# Adafruit_7in_HDMI_Backpack.net
KiCad netlist of a schematic drawn in EAGLE
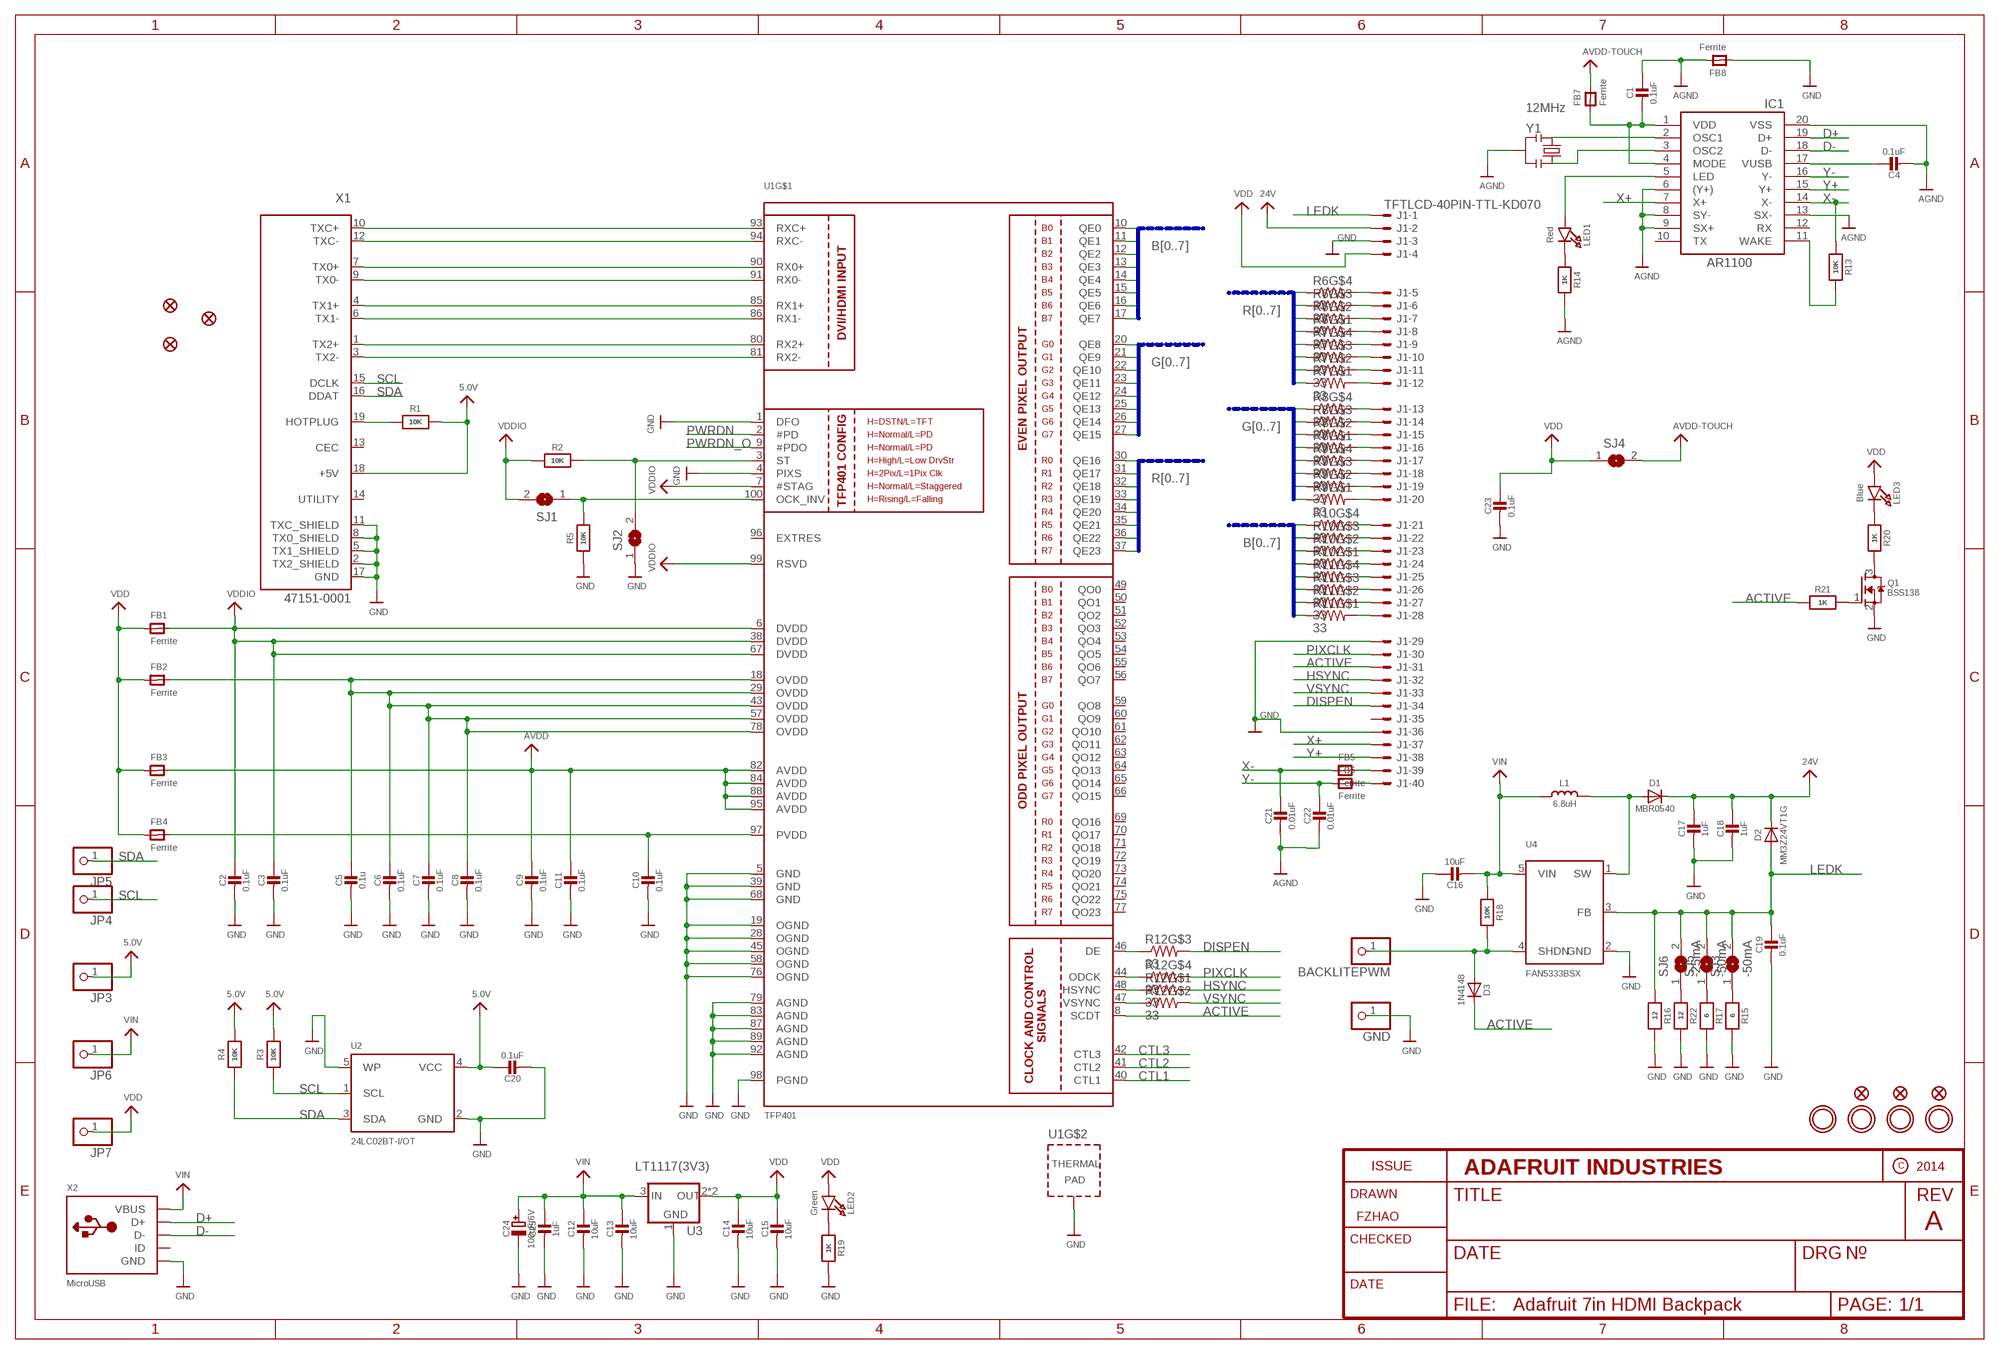
[diagram p0: schematic, sheet 1]

(export (version "E")
  (design (tool "Eeschema 10.0.6"))
  (components
    (comp (ref "BACKLITEPWM")
      (value "HEADER-1X1-SMD_MASKHELD_2X2MM")
      (footprint "eagle-import:1X01_SMD_MASKHELD_2X2MM")
      (libsource (lib "eagle-import") (part "HEADER-1X1-SMD_MASKHELD_2X2MM"))
    )
    (comp (ref "C1")
      (value "0.1uF")
      (footprint "eagle-import:0805-NO")
      (libsource (lib "eagle-import") (part "CAP_CERAMIC0805-NOOUTLINE"))
    )
    (comp (ref "C2")
      (value "0.1uF")
      (footprint "eagle-import:0805-NO")
      (libsource (lib "eagle-import") (part "CAP_CERAMIC0805-NOOUTLINE"))
    )
    (comp (ref "C3")
      (value "0.1uF")
      (footprint "eagle-import:0805-NO")
      (libsource (lib "eagle-import") (part "CAP_CERAMIC0805-NOOUTLINE"))
    )
    (comp (ref "C4")
      (value "0.1uF")
      (footprint "eagle-import:_0805MP")
      (libsource (lib "eagle-import") (part "CAP_CERAMIC_0805MP"))
    )
    (comp (ref "C5")
      (value "0.1u")
      (footprint "eagle-import:0805-NO")
      (libsource (lib "eagle-import") (part "CAP_CERAMIC0805-NOOUTLINE"))
    )
    (comp (ref "C6")
      (value "0.1uF")
      (footprint "eagle-import:_0805MP")
      (libsource (lib "eagle-import") (part "CAP_CERAMIC_0805MP"))
    )
    (comp (ref "C7")
      (value "0.1uF")
      (footprint "eagle-import:0805-NO")
      (libsource (lib "eagle-import") (part "CAP_CERAMIC0805-NOOUTLINE"))
    )
    (comp (ref "C8")
      (value "0.1uF")
      (footprint "eagle-import:0805-NO")
      (libsource (lib "eagle-import") (part "CAP_CERAMIC0805-NOOUTLINE"))
    )
    (comp (ref "C9")
      (value "0.1uF")
      (footprint "eagle-import:0805-NO")
      (libsource (lib "eagle-import") (part "CAP_CERAMIC0805-NOOUTLINE"))
    )
    (comp (ref "C10")
      (value "0.1uF")
      (footprint "eagle-import:0805-NO")
      (libsource (lib "eagle-import") (part "CAP_CERAMIC0805-NOOUTLINE"))
    )
    (comp (ref "C11")
      (value "0.1uF")
      (footprint "eagle-import:0805-NO")
      (libsource (lib "eagle-import") (part "CAP_CERAMIC0805-NOOUTLINE"))
    )
    (comp (ref "C12")
      (value "10uF")
      (footprint "eagle-import:0805-NO")
      (libsource (lib "eagle-import") (part "CAP_CERAMIC0805-NOOUTLINE"))
    )
    (comp (ref "C13")
      (value "10uF")
      (footprint "eagle-import:0805-NO")
      (libsource (lib "eagle-import") (part "CAP_CERAMIC0805-NOOUTLINE"))
    )
    (comp (ref "C14")
      (value "10uF")
      (footprint "eagle-import:0805-NO")
      (libsource (lib "eagle-import") (part "CAP_CERAMIC0805-NOOUTLINE"))
    )
    (comp (ref "C15")
      (value "10uF")
      (footprint "eagle-import:0805-NO")
      (libsource (lib "eagle-import") (part "CAP_CERAMIC0805-NOOUTLINE"))
    )
    (comp (ref "C16")
      (value "10uF")
      (footprint "eagle-import:0805-NO")
      (libsource (lib "eagle-import") (part "CAP_CERAMIC0805-NOOUTLINE"))
    )
    (comp (ref "C17")
      (value "1uF")
      (footprint "eagle-import:0805-NO")
      (libsource (lib "eagle-import") (part "CAP_CERAMIC0805-NOOUTLINE"))
    )
    (comp (ref "C18")
      (value "1uF")
      (footprint "eagle-import:0805-NO")
      (libsource (lib "eagle-import") (part "CAP_CERAMIC0805-NOOUTLINE"))
    )
    (comp (ref "C19")
      (value "0.1uF")
      (footprint "eagle-import:0805-NO")
      (libsource (lib "eagle-import") (part "CAP_CERAMIC0805-NOOUTLINE"))
    )
    (comp (ref "C20")
      (value "0.1uF")
      (footprint "eagle-import:0805-NO")
      (libsource (lib "eagle-import") (part "CAP_CERAMIC0805-NOOUTLINE"))
    )
    (comp (ref "C21")
      (value "0.01uF")
      (footprint "eagle-import:0805-NO")
      (libsource (lib "eagle-import") (part "CAP_CERAMIC0805-NOOUTLINE"))
    )
    (comp (ref "C22")
      (value "0.01uF")
      (footprint "eagle-import:0805-NO")
      (libsource (lib "eagle-import") (part "CAP_CERAMIC0805-NOOUTLINE"))
    )
    (comp (ref "C23")
      (value "0.1uF")
      (footprint "eagle-import:0805-NO")
      (libsource (lib "eagle-import") (part "CAP_CERAMIC0805-NOOUTLINE"))
    )
    (comp (ref "C24")
      (value "100uF/6V")
      (footprint "eagle-import:PANASONIC_C")
      (libsource (lib "eagle-import") (part "CAP_ELECTROLYTICPANASONIC_C"))
    )
    (comp (ref "C25")
      (value "1uF")
      (footprint "eagle-import:0805-NO")
      (libsource (lib "eagle-import") (part "CAP_CERAMIC0805-NOOUTLINE"))
    )
    (comp (ref "D1")
      (value "MBR0540")
      (footprint "eagle-import:SOD-123")
      (libsource (lib "eagle-import") (part "DIODESOD-123"))
    )
    (comp (ref "D2")
      (value "MM3Z24VT1G")
      (footprint "eagle-import:SMADIODE")
      (libsource (lib "eagle-import") (part "DIODESMA"))
    )
    (comp (ref "D3")
      (value "1N4148")
      (footprint "eagle-import:SOD-323")
      (libsource (lib "eagle-import") (part "DIODESOD-323"))
    )
    (comp (ref "FB1")
      (value "Ferrite")
      (footprint "eagle-import:_0805MP")
      (libsource (lib "eagle-import") (part "FERRITE_0805MP"))
    )
    (comp (ref "FB2")
      (value "Ferrite")
      (footprint "eagle-import:_0805MP")
      (libsource (lib "eagle-import") (part "FERRITE_0805MP"))
    )
    (comp (ref "FB3")
      (value "Ferrite")
      (footprint "eagle-import:_0805MP")
      (libsource (lib "eagle-import") (part "FERRITE_0805MP"))
    )
    (comp (ref "FB4")
      (value "Ferrite")
      (footprint "eagle-import:_0805MP")
      (libsource (lib "eagle-import") (part "FERRITE_0805MP"))
    )
    (comp (ref "FB5")
      (value "Ferrite")
      (footprint "eagle-import:_0805MP")
      (libsource (lib "eagle-import") (part "FERRITE_0805MP"))
    )
    (comp (ref "FB6")
      (value "Ferrite")
      (footprint "eagle-import:_0805MP")
      (libsource (lib "eagle-import") (part "FERRITE_0805MP"))
    )
    (comp (ref "FB7")
      (value "Ferrite")
      (footprint "eagle-import:_0805MP")
      (libsource (lib "eagle-import") (part "FERRITE_0805MP"))
    )
    (comp (ref "FB8")
      (value "Ferrite")
      (footprint "eagle-import:_0805MP")
      (libsource (lib "eagle-import") (part "FERRITE_0805MP"))
    )
    (comp (ref "FID1")
      (value "FIDUCIAL\"\"")
      (footprint "eagle-import:FIDUCIAL_1MM")
      (libsource (lib "eagle-import") (part "FIDUCIAL{dblquote}{dblquote}"))
    )
    (comp (ref "FID2")
      (value "FIDUCIAL\"\"")
      (footprint "eagle-import:FIDUCIAL_1MM")
      (libsource (lib "eagle-import") (part "FIDUCIAL{dblquote}{dblquote}"))
    )
    (comp (ref "FID3")
      (value "FIDUCIAL\"\"")
      (footprint "eagle-import:FIDUCIAL_1MM")
      (libsource (lib "eagle-import") (part "FIDUCIAL{dblquote}{dblquote}"))
    )
    (comp (ref "FID4")
      (value "FIDUCIAL\"\"")
      (footprint "eagle-import:FIDUCIAL_1MM")
      (libsource (lib "eagle-import") (part "FIDUCIAL{dblquote}{dblquote}"))
    )
    (comp (ref "FID5")
      (value "FIDUCIAL\"\"")
      (footprint "eagle-import:FIDUCIAL_1MM")
      (libsource (lib "eagle-import") (part "FIDUCIAL{dblquote}{dblquote}"))
    )
    (comp (ref "FID6")
      (value "FIDUCIAL\"\"")
      (footprint "eagle-import:FIDUCIAL_1MM")
      (libsource (lib "eagle-import") (part "FIDUCIAL{dblquote}{dblquote}"))
    )
    (comp (ref "GND")
      (value "HEADER-1X1-SMD_MASKHELD_2X2MM")
      (footprint "eagle-import:1X01_SMD_MASKHELD_2X2MM")
      (libsource (lib "eagle-import") (part "HEADER-1X1-SMD_MASKHELD_2X2MM"))
    )
    (comp (ref "IC1")
      (value "AR1100")
      (footprint "eagle-import:TSSOP20-5.3MMBODY")
      (libsource (lib "eagle-import") (part "AR1100_SSOP"))
    )
    (comp (ref "J1")
      (value "TFTLCD-40PIN-TTL-KD070")
      (footprint "eagle-import:TFTLCD-KD070GD21-40NT")
      (libsource (lib "eagle-import") (part "TFTLCD-40PIN-TTL-KD070"))
    )
    (comp (ref "JP3")
      (value "HEADER-1X1-SMD_MASKHELD_2X2MM")
      (footprint "eagle-import:1X01_SMD_MASKHELD_2X2MM")
      (libsource (lib "eagle-import") (part "HEADER-1X1-SMD_MASKHELD_2X2MM"))
    )
    (comp (ref "JP4")
      (value "HEADER-1X1-SMD_MASKHELD_2X2MM")
      (footprint "eagle-import:1X01_SMD_MASKHELD_2X2MM")
      (libsource (lib "eagle-import") (part "HEADER-1X1-SMD_MASKHELD_2X2MM"))
    )
    (comp (ref "JP5")
      (value "HEADER-1X1-SMD_MASKHELD_2X2MM")
      (footprint "eagle-import:1X01_SMD_MASKHELD_2X2MM")
      (libsource (lib "eagle-import") (part "HEADER-1X1-SMD_MASKHELD_2X2MM"))
    )
    (comp (ref "JP6")
      (value "HEADER-1X1-SMD_MASKHELD_2X2MM")
      (footprint "eagle-import:1X01_SMD_MASKHELD_2X2MM")
      (libsource (lib "eagle-import") (part "HEADER-1X1-SMD_MASKHELD_2X2MM"))
    )
    (comp (ref "JP7")
      (value "HEADER-1X1-SMD_MASKHELD_2X2MM")
      (footprint "eagle-import:1X01_SMD_MASKHELD_2X2MM")
      (libsource (lib "eagle-import") (part "HEADER-1X1-SMD_MASKHELD_2X2MM"))
    )
    (comp (ref "L1")
      (value "6.8uH")
      (footprint "eagle-import:INDUCTOR_5X5MM_NR5040_NOTHERMALS")
      (libsource (lib "eagle-import") (part "INDUCTORNR5040"))
    )
    (comp (ref "LED1")
      (value "Red")
      (footprint "eagle-import:CHIPLED_0805_NOOUTLINE")
      (libsource (lib "eagle-import") (part "LED0805_NOOUTLINE"))
    )
    (comp (ref "LED2")
      (value "Green")
      (footprint "eagle-import:CHIPLED_0805_NOOUTLINE")
      (libsource (lib "eagle-import") (part "LED0805_NOOUTLINE"))
    )
    (comp (ref "LED3")
      (value "Blue")
      (footprint "eagle-import:CHIPLED_0805_NOOUTLINE")
      (libsource (lib "eagle-import") (part "LED0805_NOOUTLINE"))
    )
    (comp (ref "Q1")
      (value "BSS138")
      (footprint "eagle-import:SOT23-WIDE")
      (libsource (lib "eagle-import") (part "MOSFET-NWIDE"))
    )
    (comp (ref "R1")
      (value "10K")
      (footprint "eagle-import:0805-NO")
      (libsource (lib "eagle-import") (part "RESISTOR0805_NOOUTLINE"))
    )
    (comp (ref "R2")
      (value "10K")
      (footprint "eagle-import:_0805MP")
      (libsource (lib "eagle-import") (part "RESISTOR_0805MP"))
    )
    (comp (ref "R3")
      (value "10K")
      (footprint "eagle-import:0805-NO")
      (libsource (lib "eagle-import") (part "RESISTOR0805_NOOUTLINE"))
    )
    (comp (ref "R4")
      (value "10K")
      (footprint "eagle-import:0805-NO")
      (libsource (lib "eagle-import") (part "RESISTOR0805_NOOUTLINE"))
    )
    (comp (ref "R5")
      (value "10K")
      (footprint "eagle-import:_0805MP")
      (libsource (lib "eagle-import") (part "RESISTOR_0805MP"))
    )
    (comp (ref "R6")
      (value "33")
      (footprint "eagle-import:RESPACK_4X0603")
      (libsource (lib "eagle-import") (part "RESISTOR_4PACK_US"))
    )
    (comp (ref "R7")
      (value "33")
      (footprint "eagle-import:RESPACK_4X0603")
      (libsource (lib "eagle-import") (part "RESISTOR_4PACK_US"))
    )
    (comp (ref "R8")
      (value "33")
      (footprint "eagle-import:RESPACK_4X0603")
      (libsource (lib "eagle-import") (part "RESISTOR_4PACK_US"))
    )
    (comp (ref "R9")
      (value "33")
      (footprint "eagle-import:RESPACK_4X0603")
      (libsource (lib "eagle-import") (part "RESISTOR_4PACK_US"))
    )
    (comp (ref "R10")
      (value "33")
      (footprint "eagle-import:RESPACK_4X0603")
      (libsource (lib "eagle-import") (part "RESISTOR_4PACK_US"))
    )
    (comp (ref "R11")
      (value "33")
      (footprint "eagle-import:RESPACK_4X0603")
      (libsource (lib "eagle-import") (part "RESISTOR_4PACK_US"))
    )
    (comp (ref "R12")
      (value "33")
      (footprint "eagle-import:RESPACK_4X0603")
      (libsource (lib "eagle-import") (part "RESISTOR_4PACK_US"))
    )
    (comp (ref "R13")
      (value "10K")
      (footprint "eagle-import:0805-NO")
      (libsource (lib "eagle-import") (part "RESISTOR0805_NOOUTLINE"))
    )
    (comp (ref "R14")
      (value "1K")
      (footprint "eagle-import:0805-NO")
      (libsource (lib "eagle-import") (part "RESISTOR0805_NOOUTLINE"))
    )
    (comp (ref "R15")
      (value "6")
      (footprint "eagle-import:0805-NO")
      (libsource (lib "eagle-import") (part "RESISTOR0805_NOOUTLINE"))
    )
    (comp (ref "R16")
      (value "12")
      (footprint "eagle-import:0805-NO")
      (libsource (lib "eagle-import") (part "RESISTOR0805_NOOUTLINE"))
    )
    (comp (ref "R17")
      (value "6")
      (footprint "eagle-import:0805-NO")
      (libsource (lib "eagle-import") (part "RESISTOR0805_NOOUTLINE"))
    )
    (comp (ref "R18")
      (value "10K")
      (footprint "eagle-import:0805-NO")
      (libsource (lib "eagle-import") (part "RESISTOR0805_NOOUTLINE"))
    )
    (comp (ref "R19")
      (value "1K")
      (footprint "eagle-import:0805-NO")
      (libsource (lib "eagle-import") (part "RESISTOR0805_NOOUTLINE"))
    )
    (comp (ref "R20")
      (value "1K")
      (footprint "eagle-import:0805-NO")
      (libsource (lib "eagle-import") (part "RESISTOR0805_NOOUTLINE"))
    )
    (comp (ref "R21")
      (value "1K")
      (footprint "eagle-import:0805-NO")
      (libsource (lib "eagle-import") (part "RESISTOR0805_NOOUTLINE"))
    )
    (comp (ref "R22")
      (value "12")
      (footprint "eagle-import:0805-NO")
      (libsource (lib "eagle-import") (part "RESISTOR0805_NOOUTLINE"))
    )
    (comp (ref "SJ1")
      (value "SOLDERJUMPER")
      (footprint "eagle-import:SOLDERJUMPER_ARROW_NOPASTE")
      (libsource (lib "eagle-import") (part "SOLDERJUMPER"))
    )
    (comp (ref "SJ2")
      (value "SOLDERJUMPER")
      (footprint "eagle-import:SOLDERJUMPER_ARROW_NOPASTE")
      (fields (field (name "BOM") "EXCLUDE"))
      (libsource (lib "eagle-import") (part "SOLDERJUMPER"))
    )
    (comp (ref "SJ3")
      (value "-50mA")
      (footprint "eagle-import:SOLDERJUMPER_CLOSEDWIRE")
      (libsource (lib "eagle-import") (part "SOLDERJUMPERCLOSED"))
    )
    (comp (ref "SJ4")
      (value "SOLDERJUMPERCLOSED")
      (footprint "eagle-import:SOLDERJUMPER_CLOSEDWIRE")
      (libsource (lib "eagle-import") (part "SOLDERJUMPERCLOSED"))
    )
    (comp (ref "SJ5")
      (value "-50mA")
      (footprint "eagle-import:SOLDERJUMPER_CLOSEDWIRE")
      (libsource (lib "eagle-import") (part "SOLDERJUMPERCLOSED"))
    )
    (comp (ref "SJ6")
      (value "-25mA")
      (footprint "eagle-import:SOLDERJUMPER_CLOSEDWIRE")
      (libsource (lib "eagle-import") (part "SOLDERJUMPERCLOSED"))
    )
    (comp (ref "U$31")
      (value "MOUNTINGHOLE3.0")
      (footprint "eagle-import:MOUNTINGHOLE_3.0_PLATED")
      (libsource (lib "eagle-import") (part "MOUNTINGHOLE3.0"))
    )
    (comp (ref "U$32")
      (value "MOUNTINGHOLE3.0")
      (footprint "eagle-import:MOUNTINGHOLE_3.0_PLATED")
      (libsource (lib "eagle-import") (part "MOUNTINGHOLE3.0"))
    )
    (comp (ref "U$33")
      (value "MOUNTINGHOLE3.0")
      (footprint "eagle-import:MOUNTINGHOLE_3.0_PLATED")
      (libsource (lib "eagle-import") (part "MOUNTINGHOLE3.0"))
    )
    (comp (ref "U$34")
      (value "MOUNTINGHOLE3.0")
      (footprint "eagle-import:MOUNTINGHOLE_3.0_PLATED")
      (libsource (lib "eagle-import") (part "MOUNTINGHOLE3.0"))
    )
    (comp (ref "U1")
      (value "TFP401")
      (footprint "eagle-import:S-PQFP-G100")
      (libsource (lib "eagle-import") (part "TFP401"))
    )
    (comp (ref "U2")
      (value "24LC02BT-I/OT")
      (footprint "eagle-import:SOT23-5")
      (libsource (lib "eagle-import") (part "EEPROM_I2C_MCP24AA32"))
    )
    (comp (ref "U3")
      (value "LT1117(3V3)")
      (footprint "eagle-import:SOT223-R")
      (libsource (lib "eagle-import") (part "VREG_SOT223"))
    )
    (comp (ref "U4")
      (value "FAN5333BSX")
      (footprint "eagle-import:SOT23-5")
      (libsource (lib "eagle-import") (part "VREG_FAN5331"))
    )
    (comp (ref "X1")
      (value "47151-0001")
      (footprint "eagle-import:HDMI_MOLEX_47151-0001_DIMLAYER")
      (libsource (lib "eagle-import") (part "HDMI_MOLEX_47151DIM"))
    )
    (comp (ref "X2")
      (value "MicroUSB")
      (footprint "eagle-import:4UCONN_20329")
      (libsource (lib "eagle-import") (part "USBMICRO_20329"))
    )
    (comp (ref "Y1")
      (value "12MHz")
      (footprint "eagle-import:RESONATOR-SMD")
      (libsource (lib "eagle-import") (part "RESONATORSMD"))
    )
  )
  (nets
    (net (code "1") (name "/ACTIVE") (class "Default")
      (node (ref "D3") (pin "C") (pinfunction "C_C") (pintype "passive"))
      (node (ref "J1") (pin "31") (pinfunction "MS_31") (pintype "passive"))
      (node (ref "R21") (pin "1") (pinfunction "1_1") (pintype "passive"))
      (node (ref "U1") (pin "8") (pinfunction "SCDT_8") (pintype "output"))
    )
    (net (code "2") (name "/B0") (class "Default")
      (node (ref "R10") (pin "4") (pinfunction "1_4") (pintype "passive"))
      (node (ref "U1") (pin "10") (pinfunction "QE0_10") (pintype "output"))
    )
    (net (code "3") (name "/B1") (class "Default")
      (node (ref "R10") (pin "3") (pinfunction "1_3") (pintype "passive"))
      (node (ref "U1") (pin "11") (pinfunction "QE1_11") (pintype "output"))
    )
    (net (code "4") (name "/B2") (class "Default")
      (node (ref "R10") (pin "2") (pinfunction "1_2") (pintype "passive"))
      (node (ref "U1") (pin "12") (pinfunction "QE2_12") (pintype "output"))
    )
    (net (code "5") (name "/B3") (class "Default")
      (node (ref "R10") (pin "1") (pinfunction "1_1") (pintype "passive"))
      (node (ref "U1") (pin "13") (pinfunction "QE3_13") (pintype "output"))
    )
    (net (code "6") (name "/B4") (class "Default")
      (node (ref "R11") (pin "4") (pinfunction "1_4") (pintype "passive"))
      (node (ref "U1") (pin "14") (pinfunction "QE4_14") (pintype "output"))
    )
    (net (code "7") (name "/B5") (class "Default")
      (node (ref "R11") (pin "3") (pinfunction "1_3") (pintype "passive"))
      (node (ref "U1") (pin "15") (pinfunction "QE5_15") (pintype "output"))
    )
    (net (code "8") (name "/B6") (class "Default")
      (node (ref "R11") (pin "2") (pinfunction "1_2") (pintype "passive"))
      (node (ref "U1") (pin "16") (pinfunction "QE6_16") (pintype "output"))
    )
    (net (code "9") (name "/B7") (class "Default")
      (node (ref "R11") (pin "1") (pinfunction "1_1") (pintype "passive"))
      (node (ref "U1") (pin "17") (pinfunction "QE7_17") (pintype "output"))
    )
    (net (code "11") (name "/CTL1") (class "Default")
      (node (ref "U1") (pin "40") (pinfunction "CTL1_40") (pintype "output"))
    )
    (net (code "12") (name "/CTL2") (class "Default")
      (node (ref "U1") (pin "41") (pinfunction "CTL2_41") (pintype "output"))
    )
    (net (code "13") (name "/CTL3") (class "Default")
      (node (ref "U1") (pin "42") (pinfunction "CTL3_42") (pintype "output"))
    )
    (net (code "14") (name "/D+") (class "Default")
      (node (ref "IC1") (pin "19") (pinfunction "D+_19") (pintype "bidirectional"))
      (node (ref "X2") (pin "D+") (pinfunction "D+_D+") (pintype "bidirectional"))
    )
    (net (code "15") (name "/D-") (class "Default")
      (node (ref "IC1") (pin "18") (pinfunction "D-_18") (pintype "bidirectional"))
      (node (ref "X2") (pin "D-") (pinfunction "D-_D-") (pintype "bidirectional"))
    )
    (net (code "16") (name "/DISPEN") (class "Default")
      (node (ref "J1") (pin "34") (pinfunction "MS_34") (pintype "passive"))
      (node (ref "R12") (pin "6") (pinfunction "2_6") (pintype "passive"))
    )
    (net (code "17") (name "/G0") (class "Default")
      (node (ref "R8") (pin "4") (pinfunction "1_4") (pintype "passive"))
      (node (ref "U1") (pin "20") (pinfunction "QE8_20") (pintype "output"))
    )
    (net (code "18") (name "/G1") (class "Default")
      (node (ref "R8") (pin "3") (pinfunction "1_3") (pintype "passive"))
      (node (ref "U1") (pin "21") (pinfunction "QE9_21") (pintype "output"))
    )
    (net (code "19") (name "/G2") (class "Default")
      (node (ref "R8") (pin "2") (pinfunction "1_2") (pintype "passive"))
      (node (ref "U1") (pin "22") (pinfunction "QE10_22") (pintype "output"))
    )
    (net (code "20") (name "/G3") (class "Default")
      (node (ref "R8") (pin "1") (pinfunction "1_1") (pintype "passive"))
      (node (ref "U1") (pin "23") (pinfunction "QE11_23") (pintype "output"))
    )
    (net (code "21") (name "/G4") (class "Default")
      (node (ref "R9") (pin "4") (pinfunction "1_4") (pintype "passive"))
      (node (ref "U1") (pin "24") (pinfunction "QE12_24") (pintype "output"))
    )
    (net (code "22") (name "/G5") (class "Default")
      (node (ref "R9") (pin "3") (pinfunction "1_3") (pintype "passive"))
      (node (ref "U1") (pin "25") (pinfunction "QE13_25") (pintype "output"))
    )
    (net (code "23") (name "/G6") (class "Default")
      (node (ref "R9") (pin "2") (pinfunction "1_2") (pintype "passive"))
      (node (ref "U1") (pin "26") (pinfunction "QE14_26") (pintype "output"))
    )
    (net (code "24") (name "/G7") (class "Default")
      (node (ref "R9") (pin "1") (pinfunction "1_1") (pintype "passive"))
      (node (ref "U1") (pin "27") (pinfunction "QE15_27") (pintype "output"))
    )
    (net (code "26") (name "/HSYNC") (class "Default")
      (node (ref "J1") (pin "32") (pinfunction "MS_32") (pintype "passive"))
      (node (ref "R12") (pin "8") (pinfunction "2_8") (pintype "passive"))
    )
    (net (code "27") (name "/LEDK") (class "Default")
      (node (ref "C19") (pin "1") (pinfunction "1_1") (pintype "passive"))
      (node (ref "D2") (pin "A") (pinfunction "A_A") (pintype "passive"))
      (node (ref "J1") (pin "1") (pinfunction "MSV_1") (pintype "passive"))
      (node (ref "R16") (pin "1") (pinfunction "1_1") (pintype "passive"))
      (node (ref "SJ3") (pin "2") (pinfunction "2_2") (pintype "passive"))
      (node (ref "SJ5") (pin "2") (pinfunction "2_2") (pintype "passive"))
      (node (ref "SJ6") (pin "2") (pinfunction "2_2") (pintype "passive"))
      (node (ref "U4") (pin "3") (pinfunction "FB_3") (pintype "bidirectional"))
    )
    (net (code "28") (name "/PIXCLK") (class "Default")
      (node (ref "J1") (pin "30") (pinfunction "MS_30") (pintype "passive"))
      (node (ref "R12") (pin "5") (pinfunction "2_5") (pintype "passive"))
    )
    (net (code "29") (name "/PWRDN") (class "Default")
      (node (ref "U1") (pin "2") (pinfunction "#PD_2") (pintype "input"))
    )
    (net (code "30") (name "/PWRDN_O") (class "Default")
      (node (ref "U1") (pin "9") (pinfunction "#PDO_9") (pintype "input"))
    )
    (net (code "31") (name "/R0") (class "Default")
      (node (ref "R6") (pin "4") (pinfunction "1_4") (pintype "passive"))
      (node (ref "U1") (pin "30") (pinfunction "QE16_30") (pintype "output"))
    )
    (net (code "32") (name "/R1") (class "Default")
      (node (ref "R6") (pin "3") (pinfunction "1_3") (pintype "passive"))
      (node (ref "U1") (pin "31") (pinfunction "QE17_31") (pintype "output"))
    )
    (net (code "33") (name "/R2") (class "Default")
      (node (ref "R6") (pin "2") (pinfunction "1_2") (pintype "passive"))
      (node (ref "U1") (pin "32") (pinfunction "QE18_32") (pintype "output"))
    )
    (net (code "34") (name "/R3") (class "Default")
      (node (ref "R6") (pin "1") (pinfunction "1_1") (pintype "passive"))
      (node (ref "U1") (pin "33") (pinfunction "QE19_33") (pintype "output"))
    )
    (net (code "35") (name "/R4") (class "Default")
      (node (ref "R7") (pin "4") (pinfunction "1_4") (pintype "passive"))
      (node (ref "U1") (pin "34") (pinfunction "QE20_34") (pintype "output"))
    )
    (net (code "36") (name "/R5") (class "Default")
      (node (ref "R7") (pin "3") (pinfunction "1_3") (pintype "passive"))
      (node (ref "U1") (pin "35") (pinfunction "QE21_35") (pintype "output"))
    )
    (net (code "37") (name "/R6") (class "Default")
      (node (ref "R7") (pin "2") (pinfunction "1_2") (pintype "passive"))
      (node (ref "U1") (pin "36") (pinfunction "QE22_36") (pintype "output"))
    )
    (net (code "38") (name "/R7") (class "Default")
      (node (ref "R7") (pin "1") (pinfunction "1_1") (pintype "passive"))
      (node (ref "U1") (pin "37") (pinfunction "QE23_37") (pintype "output"))
    )
    (net (code "40") (name "/SCL") (class "Default")
      (node (ref "JP4") (pin "1") (pinfunction "1_1") (pintype "passive"))
      (node (ref "R3") (pin "1") (pinfunction "1_1") (pintype "passive"))
      (node (ref "U2") (pin "1") (pinfunction "SCL_1") (pintype "bidirectional"))
      (node (ref "X1") (pin "15") (pinfunction "DCLK_15") (pintype "bidirectional"))
    )
    (net (code "41") (name "/SDA") (class "Default")
      (node (ref "JP5") (pin "1") (pinfunction "1_1") (pintype "passive"))
      (node (ref "R4") (pin "1") (pinfunction "1_1") (pintype "passive"))
      (node (ref "U2") (pin "3") (pinfunction "SDA_3") (pintype "bidirectional"))
      (node (ref "X1") (pin "16") (pinfunction "DDAT_16") (pintype "bidirectional"))
    )
    (net (code "42") (name "/VSYNC") (class "Default")
      (node (ref "J1") (pin "33") (pinfunction "MS_33") (pintype "passive"))
      (node (ref "R12") (pin "7") (pinfunction "2_7") (pintype "passive"))
    )
    (net (code "43") (name "/X+") (class "Default")
      (node (ref "IC1") (pin "7") (pinfunction "X+_7") (pintype "bidirectional"))
      (node (ref "J1") (pin "37") (pinfunction "MS_37") (pintype "passive"))
    )
    (net (code "44") (name "/X-") (class "Default")
      (node (ref "C21") (pin "1") (pinfunction "1_1") (pintype "passive"))
      (node (ref "FB5") (pin "1") (pinfunction "P$1_1") (pintype "passive"))
      (node (ref "IC1") (pin "14") (pinfunction "X-_14") (pintype "bidirectional"))
      (node (ref "R13") (pin "1") (pinfunction "1_1") (pintype "passive"))
    )
    (net (code "45") (name "/Y+") (class "Default")
      (node (ref "IC1") (pin "15") (pinfunction "Y+_15") (pintype "bidirectional"))
      (node (ref "J1") (pin "38") (pinfunction "MS_38") (pintype "passive"))
    )
    (net (code "46") (name "/Y-") (class "Default")
      (node (ref "C22") (pin "1") (pinfunction "1_1") (pintype "passive"))
      (node (ref "FB6") (pin "1") (pinfunction "P$1_1") (pintype "passive"))
      (node (ref "IC1") (pin "16") (pinfunction "Y-_16") (pintype "bidirectional"))
    )
    (net (code "47") (name "5.0V") (class "Default")
      (node (ref "C20") (pin "1") (pinfunction "1_1") (pintype "passive"))
      (node (ref "JP3") (pin "1") (pinfunction "1_1") (pintype "passive"))
      (node (ref "R1") (pin "2") (pinfunction "2_2") (pintype "passive"))
      (node (ref "R3") (pin "2") (pinfunction "2_2") (pintype "passive"))
      (node (ref "R4") (pin "2") (pinfunction "2_2") (pintype "passive"))
      (node (ref "U2") (pin "4") (pinfunction "VCC_4") (pintype "bidirectional"))
      (node (ref "X1") (pin "18") (pinfunction "+5V_18") (pintype "power_in"))
    )
    (net (code "48") (name "24V") (class "Default")
      (node (ref "C17") (pin "1") (pinfunction "1_1") (pintype "passive"))
      (node (ref "C18") (pin "1") (pinfunction "1_1") (pintype "passive"))
      (node (ref "D1") (pin "C") (pinfunction "C_C") (pintype "passive"))
      (node (ref "D2") (pin "C") (pinfunction "C_C") (pintype "passive"))
      (node (ref "J1") (pin "2") (pinfunction "MS_2") (pintype "passive"))
    )
    (net (code "49") (name "AGND") (class "Default")
      (node (ref "C1") (pin "1") (pinfunction "1_1") (pintype "passive"))
      (node (ref "C21") (pin "2") (pinfunction "2_2") (pintype "passive"))
      (node (ref "C22") (pin "2") (pinfunction "2_2") (pintype "passive"))
      (node (ref "C4") (pin "2") (pinfunction "2_2") (pintype "passive"))
      (node (ref "FB8") (pin "2") (pinfunction "P$2_2") (pintype "passive"))
      (node (ref "IC1") (pin "13") (pinfunction "SX-_13") (pintype "bidirectional"))
      (node (ref "IC1") (pin "20") (pinfunction "VSS_20") (pintype "power_in"))
      (node (ref "IC1") (pin "6") (pinfunction "(Y+)_6") (pintype "bidirectional"))
      (node (ref "IC1") (pin "8") (pinfunction "SY-_8") (pintype "bidirectional"))
      (node (ref "IC1") (pin "9") (pinfunction "SX+_9") (pintype "bidirectional"))
      (node (ref "R14") (pin "2") (pinfunction "2_2") (pintype "passive"))
      (node (ref "Y1") (pin "2") (pinfunction "2_2") (pintype "passive"))
    )
    (net (code "50") (name "AVDD") (class "Default")
      (node (ref "C11") (pin "1") (pinfunction "1_1") (pintype "passive"))
      (node (ref "C9") (pin "1") (pinfunction "1_1") (pintype "passive"))
      (node (ref "FB3") (pin "2") (pinfunction "P$2_2") (pintype "passive"))
      (node (ref "U1") (pin "82") (pinfunction "AVDD_82") (pintype "power_in"))
      (node (ref "U1") (pin "84") (pinfunction "AVDD_84") (pintype "power_in"))
      (node (ref "U1") (pin "88") (pinfunction "AVDD_88") (pintype "power_in"))
      (node (ref "U1") (pin "95") (pinfunction "AVDD_95") (pintype "power_in"))
    )
    (net (code "51") (name "AVDD-TOUCH") (class "Default")
      (node (ref "FB7") (pin "2") (pinfunction "P$2_2") (pintype "passive"))
      (node (ref "SJ4") (pin "2") (pinfunction "2_2") (pintype "passive"))
    )
    (net (code "52") (name "GND") (class "Default")
      (node (ref "C10") (pin "2") (pinfunction "2_2") (pintype "passive"))
      (node (ref "C11") (pin "2") (pinfunction "2_2") (pintype "passive"))
      (node (ref "C12") (pin "2") (pinfunction "2_2") (pintype "passive"))
      (node (ref "C13") (pin "2") (pinfunction "2_2") (pintype "passive"))
      (node (ref "C14") (pin "2") (pinfunction "2_2") (pintype "passive"))
      (node (ref "C15") (pin "2") (pinfunction "2_2") (pintype "passive"))
      (node (ref "C16") (pin "1") (pinfunction "1_1") (pintype "passive"))
      (node (ref "C17") (pin "2") (pinfunction "2_2") (pintype "passive"))
      (node (ref "C18") (pin "2") (pinfunction "2_2") (pintype "passive"))
      (node (ref "C19") (pin "2") (pinfunction "2_2") (pintype "passive"))
      (node (ref "C2") (pin "2") (pinfunction "2_2") (pintype "passive"))
      (node (ref "C20") (pin "2") (pinfunction "2_2") (pintype "passive"))
      (node (ref "C23") (pin "2") (pinfunction "2_2") (pintype "passive"))
      (node (ref "C24") (pin "-") (pinfunction "-_-") (pintype "passive"))
      (node (ref "C25") (pin "2") (pinfunction "2_2") (pintype "passive"))
      (node (ref "C3") (pin "2") (pinfunction "2_2") (pintype "passive"))
      (node (ref "C5") (pin "2") (pinfunction "2_2") (pintype "passive"))
      (node (ref "C6") (pin "2") (pinfunction "2_2") (pintype "passive"))
      (node (ref "C7") (pin "2") (pinfunction "2_2") (pintype "passive"))
      (node (ref "C8") (pin "2") (pinfunction "2_2") (pintype "passive"))
      (node (ref "C9") (pin "2") (pinfunction "2_2") (pintype "passive"))
      (node (ref "FB8") (pin "1") (pinfunction "P$1_1") (pintype "passive"))
      (node (ref "GND") (pin "1") (pinfunction "1_1") (pintype "passive"))
      (node (ref "J1") (pin "29") (pinfunction "MS_29") (pintype "passive"))
      (node (ref "J1") (pin "3") (pinfunction "MS_3") (pintype "passive"))
      (node (ref "J1") (pin "36") (pinfunction "MS_36") (pintype "passive"))
      (node (ref "Q1") (pin "2") (pinfunction "S_2") (pintype "bidirectional"))
      (node (ref "R15") (pin "2") (pinfunction "2_2") (pintype "passive"))
      (node (ref "R16") (pin "2") (pinfunction "2_2") (pintype "passive"))
      (node (ref "R17") (pin "2") (pinfunction "2_2") (pintype "passive"))
      (node (ref "R19") (pin "2") (pinfunction "2_2") (pintype "passive"))
      (node (ref "R22") (pin "2") (pinfunction "2_2") (pintype "passive"))
      (node (ref "R5") (pin "1") (pinfunction "1_1") (pintype "passive"))
      (node (ref "SJ2") (pin "1") (pinfunction "1_1") (pintype "passive"))
      (node (ref "U1") (pin "1") (pinfunction "DFO_1") (pintype "input"))
      (node (ref "U1") (pin "19") (pinfunction "OGND_19") (pintype "power_in"))
      (node (ref "U1") (pin "28") (pinfunction "OGND_28") (pintype "power_in"))
      (node (ref "U1") (pin "39") (pinfunction "GND_39") (pintype "power_in"))
      (node (ref "U1") (pin "4") (pinfunction "PIXS_4") (pintype "input"))
      (node (ref "U1") (pin "45") (pinfunction "OGND_45") (pintype "power_in"))
      (node (ref "U1") (pin "5") (pinfunction "GND_5") (pintype "power_in"))
      (node (ref "U1") (pin "58") (pinfunction "OGND_58") (pintype "power_in"))
      (node (ref "U1") (pin "68") (pinfunction "GND_68") (pintype "power_in"))
      (node (ref "U1") (pin "76") (pinfunction "OGND_76") (pintype "power_in"))
      (node (ref "U1") (pin "79") (pinfunction "AGND_79") (pintype "power_in"))
      (node (ref "U1") (pin "83") (pinfunction "AGND_83") (pintype "power_in"))
      (node (ref "U1") (pin "87") (pinfunction "AGND_87") (pintype "power_in"))
      (node (ref "U1") (pin "89") (pinfunction "AGND_89") (pintype "power_in"))
      (node (ref "U1") (pin "92") (pinfunction "AGND_92") (pintype "power_in"))
      (node (ref "U1") (pin "98") (pinfunction "PGND_98") (pintype "power_in"))
      (node (ref "U1") (pin "P$1") (pinfunction "TP_P$1") (pintype "power_in"))
      (node (ref "U1") (pin "P$10") (pinfunction "TP_P$10") (pintype "power_in"))
      (node (ref "U1") (pin "P$11") (pinfunction "TP_P$11") (pintype "power_in"))
      (node (ref "U1") (pin "P$12") (pinfunction "TP_P$12") (pintype "power_in"))
      (node (ref "U1") (pin "P$13") (pinfunction "TP_P$13") (pintype "power_in"))
      (node (ref "U1") (pin "P$14") (pinfunction "TP_P$14") (pintype "power_in"))
      (node (ref "U1") (pin "P$15") (pinfunction "TP_P$15") (pintype "power_in"))
      (node (ref "U1") (pin "P$16") (pinfunction "TP_P$16") (pintype "power_in"))
      (node (ref "U1") (pin "P$2") (pinfunction "TP_P$2") (pintype "power_in"))
      (node (ref "U1") (pin "P$3") (pinfunction "TP_P$3") (pintype "power_in"))
      (node (ref "U1") (pin "P$4") (pinfunction "TP_P$4") (pintype "power_in"))
      (node (ref "U1") (pin "P$5") (pinfunction "TP_P$5") (pintype "power_in"))
      (node (ref "U1") (pin "P$6") (pinfunction "TP_P$6") (pintype "power_in"))
      (node (ref "U1") (pin "P$7") (pinfunction "TP_P$7") (pintype "power_in"))
      (node (ref "U1") (pin "P$8") (pinfunction "TP_P$8") (pintype "power_in"))
      (node (ref "U1") (pin "P$9") (pinfunction "TP_P$9") (pintype "power_in"))
      (node (ref "U1") (pin "THERMAL") (pinfunction "TP_THERMAL") (pintype "power_in"))
      (node (ref "U2") (pin "2") (pinfunction "GND_2") (pintype "bidirectional"))
      (node (ref "U2") (pin "5") (pinfunction "WP_5") (pintype "bidirectional"))
      (node (ref "U3") (pin "1") (pinfunction "GND_1") (pintype "power_in"))
      (node (ref "U4") (pin "2") (pinfunction "GND_2") (pintype "bidirectional"))
      (node (ref "X1") (pin "11") (pinfunction "TXC_SHIELD_11") (pintype "power_in"))
      (node (ref "X1") (pin "17") (pinfunction "GND_17") (pintype "power_in"))
      (node (ref "X1") (pin "2") (pinfunction "TX2_SHIELD_2") (pintype "power_in"))
      (node (ref "X1") (pin "5") (pinfunction "TX1_SHIELD_5") (pintype "power_in"))
      (node (ref "X1") (pin "8") (pinfunction "TX0_SHIELD_8") (pintype "power_in"))
      (node (ref "X2") (pin "BASE@1") (pinfunction "GND_BASE@1") (pintype "power_in"))
      (node (ref "X2") (pin "BASE@2") (pinfunction "GND_BASE@2") (pintype "power_in"))
      (node (ref "X2") (pin "GND") (pinfunction "GND_GND") (pintype "power_in"))
      (node (ref "X2") (pin "SPRT@1") (pinfunction "GND_SPRT@1") (pintype "power_in"))
      (node (ref "X2") (pin "SPRT@2") (pinfunction "GND_SPRT@2") (pintype "power_in"))
      (node (ref "X2") (pin "SPRT@3") (pinfunction "GND_SPRT@3") (pintype "power_in"))
      (node (ref "X2") (pin "SPRT@4") (pinfunction "GND_SPRT@4") (pintype "power_in"))
    )
    (net (code "53") (name "Net-(FB2-P$2)") (class "Default")
      (node (ref "C5") (pin "1") (pinfunction "1_1") (pintype "passive"))
      (node (ref "C6") (pin "1") (pinfunction "1_1") (pintype "passive"))
      (node (ref "C7") (pin "1") (pinfunction "1_1") (pintype "passive"))
      (node (ref "C8") (pin "1") (pinfunction "1_1") (pintype "passive"))
      (node (ref "FB2") (pin "2") (pinfunction "P$2_2") (pintype "passive"))
      (node (ref "U1") (pin "18") (pinfunction "OVDD_18") (pintype "power_in"))
      (node (ref "U1") (pin "29") (pinfunction "OVDD_29") (pintype "power_in"))
      (node (ref "U1") (pin "43") (pinfunction "OVDD_43") (pintype "power_in"))
      (node (ref "U1") (pin "57") (pinfunction "OVDD_57") (pintype "power_in"))
      (node (ref "U1") (pin "78") (pinfunction "OVDD_78") (pintype "power_in"))
    )
    (net (code "54") (name "Net-(FB4-P$2)") (class "Default")
      (node (ref "C10") (pin "1") (pinfunction "1_1") (pintype "passive"))
      (node (ref "FB4") (pin "2") (pinfunction "P$2_2") (pintype "passive"))
      (node (ref "U1") (pin "97") (pinfunction "PVDD_97") (pintype "power_in"))
    )
    (net (code "55") (name "Net-(FB5-P$2)") (class "Default")
      (node (ref "FB5") (pin "2") (pinfunction "P$2_2") (pintype "passive"))
      (node (ref "J1") (pin "39") (pinfunction "MS_39") (pintype "passive"))
    )
    (net (code "56") (name "Net-(FB6-P$2)") (class "Default")
      (node (ref "FB6") (pin "2") (pinfunction "P$2_2") (pintype "passive"))
      (node (ref "J1") (pin "40") (pinfunction "MS_40") (pintype "passive"))
    )
    (net (code "57") (name "Net-(FB7-P$1)") (class "Default")
      (node (ref "C1") (pin "2") (pinfunction "2_2") (pintype "passive"))
      (node (ref "FB7") (pin "1") (pinfunction "P$1_1") (pintype "passive"))
      (node (ref "IC1") (pin "1") (pinfunction "VDD_1") (pintype "power_in"))
      (node (ref "IC1") (pin "4") (pinfunction "MODE_4") (pintype "input"))
    )
    (net (code "58") (name "Net-(IC1-LED)") (class "Default")
      (node (ref "IC1") (pin "5") (pinfunction "LED_5") (pintype "output"))
      (node (ref "LED1") (pin "A") (pinfunction "A_A") (pintype "passive"))
    )
    (net (code "59") (name "Net-(IC1-OSC1)") (class "Default")
      (node (ref "IC1") (pin "2") (pinfunction "OSC1_2") (pintype "passive"))
      (node (ref "Y1") (pin "1") (pinfunction "1_1") (pintype "passive"))
    )
    (net (code "60") (name "Net-(IC1-OSC2)") (class "Default")
      (node (ref "IC1") (pin "3") (pinfunction "OSC2_3") (pintype "passive"))
      (node (ref "Y1") (pin "3") (pinfunction "3_3") (pintype "passive"))
    )
    (net (code "61") (name "Net-(IC1-VUSB)") (class "Default")
      (node (ref "C4") (pin "1") (pinfunction "1_1") (pintype "passive"))
      (node (ref "IC1") (pin "17") (pinfunction "VUSB_17") (pintype "power_in"))
    )
    (net (code "62") (name "Net-(IC1-WAKE)") (class "Default")
      (node (ref "IC1") (pin "11") (pinfunction "WAKE_11") (pintype "input"))
      (node (ref "R13") (pin "2") (pinfunction "2_2") (pintype "passive"))
    )
    (net (code "63") (name "Net-(J1AJ-MS)") (class "Default")
      (node (ref "J1") (pin "5") (pinfunction "MS_5") (pintype "passive"))
      (node (ref "R6") (pin "5") (pinfunction "2_5") (pintype "passive"))
    )
    (net (code "64") (name "Net-(J1AK-MS)") (class "Default")
      (node (ref "J1") (pin "6") (pinfunction "MS_6") (pintype "passive"))
      (node (ref "R6") (pin "6") (pinfunction "2_6") (pintype "passive"))
    )
    (net (code "65") (name "Net-(J1AL-MS)") (class "Default")
      (node (ref "J1") (pin "7") (pinfunction "MS_7") (pintype "passive"))
      (node (ref "R6") (pin "7") (pinfunction "2_7") (pintype "passive"))
    )
    (net (code "66") (name "Net-(J1AM-MS)") (class "Default")
      (node (ref "J1") (pin "8") (pinfunction "MS_8") (pintype "passive"))
      (node (ref "R6") (pin "8") (pinfunction "2_8") (pintype "passive"))
    )
    (net (code "67") (name "Net-(J1AN-MS)") (class "Default")
      (node (ref "J1") (pin "9") (pinfunction "MS_9") (pintype "passive"))
      (node (ref "R7") (pin "5") (pinfunction "2_5") (pintype "passive"))
    )
    (net (code "68") (name "Net-(J1B-MS)") (class "Default")
      (node (ref "J1") (pin "10") (pinfunction "MS_10") (pintype "passive"))
      (node (ref "R7") (pin "6") (pinfunction "2_6") (pintype "passive"))
    )
    (net (code "69") (name "Net-(J1C-MS)") (class "Default")
      (node (ref "J1") (pin "11") (pinfunction "MS_11") (pintype "passive"))
      (node (ref "R7") (pin "7") (pinfunction "2_7") (pintype "passive"))
    )
    (net (code "70") (name "Net-(J1D-MS)") (class "Default")
      (node (ref "J1") (pin "12") (pinfunction "MS_12") (pintype "passive"))
      (node (ref "R7") (pin "8") (pinfunction "2_8") (pintype "passive"))
    )
    (net (code "71") (name "Net-(J1E-MS)") (class "Default")
      (node (ref "J1") (pin "13") (pinfunction "MS_13") (pintype "passive"))
      (node (ref "R8") (pin "5") (pinfunction "2_5") (pintype "passive"))
    )
    (net (code "72") (name "Net-(J1F-MS)") (class "Default")
      (node (ref "J1") (pin "14") (pinfunction "MS_14") (pintype "passive"))
      (node (ref "R8") (pin "6") (pinfunction "2_6") (pintype "passive"))
    )
    (net (code "73") (name "Net-(J1G-MS)") (class "Default")
      (node (ref "J1") (pin "15") (pinfunction "MS_15") (pintype "passive"))
      (node (ref "R8") (pin "7") (pinfunction "2_7") (pintype "passive"))
    )
    (net (code "74") (name "Net-(J1H-MS)") (class "Default")
      (node (ref "J1") (pin "16") (pinfunction "MS_16") (pintype "passive"))
      (node (ref "R8") (pin "8") (pinfunction "2_8") (pintype "passive"))
    )
    (net (code "75") (name "Net-(J1I-MS)") (class "Default")
      (node (ref "J1") (pin "17") (pinfunction "MS_17") (pintype "passive"))
      (node (ref "R9") (pin "5") (pinfunction "2_5") (pintype "passive"))
    )
    (net (code "76") (name "Net-(J1J-MS)") (class "Default")
      (node (ref "J1") (pin "18") (pinfunction "MS_18") (pintype "passive"))
      (node (ref "R9") (pin "6") (pinfunction "2_6") (pintype "passive"))
    )
    (net (code "77") (name "Net-(J1K-MS)") (class "Default")
      (node (ref "J1") (pin "19") (pinfunction "MS_19") (pintype "passive"))
      (node (ref "R9") (pin "7") (pinfunction "2_7") (pintype "passive"))
    )
    (net (code "78") (name "Net-(J1M-MS)") (class "Default")
      (node (ref "J1") (pin "20") (pinfunction "MS_20") (pintype "passive"))
      (node (ref "R9") (pin "8") (pinfunction "2_8") (pintype "passive"))
    )
    (net (code "79") (name "Net-(J1N-MS)") (class "Default")
      (node (ref "J1") (pin "21") (pinfunction "MS_21") (pintype "passive"))
      (node (ref "R10") (pin "5") (pinfunction "2_5") (pintype "passive"))
    )
    (net (code "80") (name "Net-(J1O-MS)") (class "Default")
      (node (ref "J1") (pin "22") (pinfunction "MS_22") (pintype "passive"))
      (node (ref "R10") (pin "6") (pinfunction "2_6") (pintype "passive"))
    )
    (net (code "81") (name "Net-(J1P-MS)") (class "Default")
      (node (ref "J1") (pin "23") (pinfunction "MS_23") (pintype "passive"))
      (node (ref "R10") (pin "7") (pinfunction "2_7") (pintype "passive"))
    )
    (net (code "82") (name "Net-(J1Q-MS)") (class "Default")
      (node (ref "J1") (pin "24") (pinfunction "MS_24") (pintype "passive"))
      (node (ref "R10") (pin "8") (pinfunction "2_8") (pintype "passive"))
    )
    (net (code "83") (name "Net-(J1R-MS)") (class "Default")
      (node (ref "J1") (pin "25") (pinfunction "MS_25") (pintype "passive"))
      (node (ref "R11") (pin "5") (pinfunction "2_5") (pintype "passive"))
    )
    (net (code "84") (name "Net-(J1S-MS)") (class "Default")
      (node (ref "J1") (pin "26") (pinfunction "MS_26") (pintype "passive"))
      (node (ref "R11") (pin "6") (pinfunction "2_6") (pintype "passive"))
    )
    (net (code "85") (name "Net-(J1T-MS)") (class "Default")
      (node (ref "J1") (pin "27") (pinfunction "MS_27") (pintype "passive"))
      (node (ref "R11") (pin "7") (pinfunction "2_7") (pintype "passive"))
    )
    (net (code "86") (name "Net-(J1U-MS)") (class "Default")
      (node (ref "J1") (pin "28") (pinfunction "MS_28") (pintype "passive"))
      (node (ref "R11") (pin "8") (pinfunction "2_8") (pintype "passive"))
    )
    (net (code "87") (name "Net-(L1-2)") (class "Default")
      (node (ref "D1") (pin "A") (pinfunction "A_A") (pintype "passive"))
      (node (ref "L1") (pin "P$2") (pinfunction "2_P$2") (pintype "passive"))
      (node (ref "U4") (pin "1") (pinfunction "SW_1") (pintype "bidirectional"))
    )
    (net (code "88") (name "Net-(LED1-PadC)") (class "Default")
      (node (ref "LED1") (pin "C") (pinfunction "C_C") (pintype "passive"))
      (node (ref "R14") (pin "1") (pinfunction "1_1") (pintype "passive"))
    )
    (net (code "89") (name "Net-(LED2-PadC)") (class "Default")
      (node (ref "LED2") (pin "C") (pinfunction "C_C") (pintype "passive"))
      (node (ref "R19") (pin "1") (pinfunction "1_1") (pintype "passive"))
    )
    (net (code "90") (name "Net-(LED3-PadC)") (class "Default")
      (node (ref "LED3") (pin "C") (pinfunction "C_C") (pintype "passive"))
      (node (ref "R20") (pin "1") (pinfunction "1_1") (pintype "passive"))
    )
    (net (code "91") (name "Net-(Q1-D)") (class "Default")
      (node (ref "Q1") (pin "3") (pinfunction "D_3") (pintype "bidirectional"))
      (node (ref "R20") (pin "2") (pinfunction "2_2") (pintype "passive"))
    )
    (net (code "92") (name "Net-(Q1-G)") (class "Default")
      (node (ref "Q1") (pin "1") (pinfunction "G_1") (pintype "bidirectional"))
      (node (ref "R21") (pin "2") (pinfunction "2_2") (pintype "passive"))
    )
    (net (code "93") (name "Net-(R12B-1)") (class "Default")
      (node (ref "R12") (pin "2") (pinfunction "1_2") (pintype "passive"))
      (node (ref "U1") (pin "47") (pinfunction "VSYNC_47") (pintype "output"))
    )
    (net (code "94") (name "Net-(R12C-1)") (class "Default")
      (node (ref "R12") (pin "3") (pinfunction "1_3") (pintype "passive"))
      (node (ref "U1") (pin "46") (pinfunction "DE_46") (pintype "output"))
    )
    (net (code "95") (name "Net-(R12D-1)") (class "Default")
      (node (ref "R12") (pin "4") (pinfunction "1_4") (pintype "passive"))
      (node (ref "U1") (pin "44") (pinfunction "ODCK_44") (pintype "output"))
    )
    (net (code "96") (name "Net-(R15-Pad1)") (class "Default")
      (node (ref "R15") (pin "1") (pinfunction "1_1") (pintype "passive"))
      (node (ref "SJ3") (pin "1") (pinfunction "1_1") (pintype "passive"))
    )
    (net (code "97") (name "Net-(R17-Pad1)") (class "Default")
      (node (ref "R17") (pin "1") (pinfunction "1_1") (pintype "passive"))
      (node (ref "SJ5") (pin "1") (pinfunction "1_1") (pintype "passive"))
    )
    (net (code "98") (name "Net-(R22-Pad1)") (class "Default")
      (node (ref "R22") (pin "1") (pinfunction "1_1") (pintype "passive"))
      (node (ref "SJ6") (pin "1") (pinfunction "1_1") (pintype "passive"))
    )
    (net (code "99") (name "Net-(U1A-HSYNC)") (class "Default")
      (node (ref "R12") (pin "1") (pinfunction "1_1") (pintype "passive"))
      (node (ref "U1") (pin "48") (pinfunction "HSYNC_48") (pintype "output"))
    )
    (net (code "100") (name "Net-(U1A-OCK_INV)") (class "Default")
      (node (ref "R5") (pin "2") (pinfunction "2_2") (pintype "passive"))
      (node (ref "SJ1") (pin "1") (pinfunction "1_1") (pintype "passive"))
      (node (ref "U1") (pin "100") (pinfunction "OCK_INV_100") (pintype "input"))
    )
    (net (code "101") (name "Net-(U1A-RX0+)") (class "Default")
      (node (ref "U1") (pin "90") (pinfunction "RX0+_90") (pintype "input"))
      (node (ref "X1") (pin "7") (pinfunction "TX0+_7") (pintype "bidirectional"))
    )
    (net (code "102") (name "Net-(U1A-RX0-)") (class "Default")
      (node (ref "U1") (pin "91") (pinfunction "RX0-_91") (pintype "input"))
      (node (ref "X1") (pin "9") (pinfunction "TX0-_9") (pintype "bidirectional"))
    )
    (net (code "103") (name "Net-(U1A-RX1+)") (class "Default")
      (node (ref "U1") (pin "85") (pinfunction "RX1+_85") (pintype "input"))
      (node (ref "X1") (pin "4") (pinfunction "TX1+_4") (pintype "bidirectional"))
    )
    (net (code "104") (name "Net-(U1A-RX1-)") (class "Default")
      (node (ref "U1") (pin "86") (pinfunction "RX1-_86") (pintype "input"))
      (node (ref "X1") (pin "6") (pinfunction "TX1-_6") (pintype "bidirectional"))
    )
    (net (code "105") (name "Net-(U1A-RX2+)") (class "Default")
      (node (ref "U1") (pin "80") (pinfunction "RX2+_80") (pintype "input"))
      (node (ref "X1") (pin "1") (pinfunction "TX2+_1") (pintype "bidirectional"))
    )
    (net (code "106") (name "Net-(U1A-RX2-)") (class "Default")
      (node (ref "U1") (pin "81") (pinfunction "RX2-_81") (pintype "input"))
      (node (ref "X1") (pin "3") (pinfunction "TX2-_3") (pintype "bidirectional"))
    )
    (net (code "107") (name "Net-(U1A-RXC+)") (class "Default")
      (node (ref "U1") (pin "93") (pinfunction "RXC+_93") (pintype "input"))
      (node (ref "X1") (pin "10") (pinfunction "TXC+_10") (pintype "bidirectional"))
    )
    (net (code "108") (name "Net-(U1A-RXC-)") (class "Default")
      (node (ref "U1") (pin "94") (pinfunction "RXC-_94") (pintype "input"))
      (node (ref "X1") (pin "12") (pinfunction "TXC-_12") (pintype "bidirectional"))
    )
    (net (code "109") (name "Net-(U1A-ST)") (class "Default")
      (node (ref "R2") (pin "2") (pinfunction "2_2") (pintype "passive"))
      (node (ref "SJ2") (pin "2") (pinfunction "2_2") (pintype "passive"))
      (node (ref "U1") (pin "3") (pinfunction "ST_3") (pintype "input"))
    )
    (net (code "110") (name "Net-(U4-SHDN)") (class "Default")
      (node (ref "BACKLITEPWM") (pin "1") (pinfunction "1_1") (pintype "passive"))
      (node (ref "D3") (pin "A") (pinfunction "A_A") (pintype "passive"))
      (node (ref "R18") (pin "2") (pinfunction "2_2") (pintype "passive"))
      (node (ref "U4") (pin "4") (pinfunction "SHDN_4") (pintype "bidirectional"))
    )
    (net (code "111") (name "Net-(X1A-HOTPLUG)") (class "Default")
      (node (ref "R1") (pin "1") (pinfunction "1_1") (pintype "passive"))
      (node (ref "X1") (pin "19") (pinfunction "HOTPLUG_19") (pintype "bidirectional"))
    )
    (net (code "112") (name "VDD") (class "Default")
      (node (ref "C14") (pin "1") (pinfunction "1_1") (pintype "passive"))
      (node (ref "C15") (pin "1") (pinfunction "1_1") (pintype "passive"))
      (node (ref "C23") (pin "1") (pinfunction "1_1") (pintype "passive"))
      (node (ref "FB1") (pin "1") (pinfunction "P$1_1") (pintype "passive"))
      (node (ref "FB2") (pin "1") (pinfunction "P$1_1") (pintype "passive"))
      (node (ref "FB3") (pin "1") (pinfunction "P$1_1") (pintype "passive"))
      (node (ref "FB4") (pin "1") (pinfunction "P$1_1") (pintype "passive"))
      (node (ref "J1") (pin "4") (pinfunction "MS_4") (pintype "passive"))
      (node (ref "JP7") (pin "1") (pinfunction "1_1") (pintype "passive"))
      (node (ref "LED2") (pin "A") (pinfunction "A_A") (pintype "passive"))
      (node (ref "LED3") (pin "A") (pinfunction "A_A") (pintype "passive"))
      (node (ref "SJ4") (pin "1") (pinfunction "1_1") (pintype "passive"))
      (node (ref "U3") (pin "2") (pinfunction "OUT_2") (pintype "power_in"))
      (node (ref "U3") (pin "4") (pinfunction "OUT_4") (pintype "power_in"))
    )
    (net (code "113") (name "VDDIO") (class "Default")
      (node (ref "C2") (pin "1") (pinfunction "1_1") (pintype "passive"))
      (node (ref "C3") (pin "1") (pinfunction "1_1") (pintype "passive"))
      (node (ref "FB1") (pin "2") (pinfunction "P$2_2") (pintype "passive"))
      (node (ref "R2") (pin "1") (pinfunction "1_1") (pintype "passive"))
      (node (ref "SJ1") (pin "2") (pinfunction "2_2") (pintype "passive"))
      (node (ref "U1") (pin "38") (pinfunction "DVDD_38") (pintype "power_in"))
      (node (ref "U1") (pin "6") (pinfunction "DVDD_6") (pintype "power_in"))
      (node (ref "U1") (pin "67") (pinfunction "DVDD_67") (pintype "power_in"))
      (node (ref "U1") (pin "7") (pinfunction "#STAG_7") (pintype "input"))
      (node (ref "U1") (pin "99") (pinfunction "RSVD_99") (pintype "input"))
    )
    (net (code "114") (name "VIN") (class "Default")
      (node (ref "C12") (pin "1") (pinfunction "1_1") (pintype "passive"))
      (node (ref "C13") (pin "1") (pinfunction "1_1") (pintype "passive"))
      (node (ref "C16") (pin "2") (pinfunction "2_2") (pintype "passive"))
      (node (ref "C24") (pin "+") (pinfunction "+_+") (pintype "passive"))
      (node (ref "C25") (pin "1") (pinfunction "1_1") (pintype "passive"))
      (node (ref "JP6") (pin "1") (pinfunction "1_1") (pintype "passive"))
      (node (ref "L1") (pin "P$1") (pinfunction "1_P$1") (pintype "passive"))
      (node (ref "R18") (pin "1") (pinfunction "1_1") (pintype "passive"))
      (node (ref "U3") (pin "3") (pinfunction "IN_3") (pintype "power_in"))
      (node (ref "U4") (pin "5") (pinfunction "VIN_5") (pintype "bidirectional"))
      (node (ref "X2") (pin "VBUS") (pinfunction "VBUS_VBUS") (pintype "power_in"))
    )
    (net (code "115") (name "unconnected-(IC1-RX-Pad12)") (class "Default")
      (node (ref "IC1") (pin "12") (pinfunction "RX_12") (pintype "input"))
    )
    (net (code "116") (name "unconnected-(IC1-TX-Pad10)") (class "Default")
      (node (ref "IC1") (pin "10") (pinfunction "TX_10") (pintype "output"))
    )
    (net (code "117") (name "unconnected-(J1AC-MS-Pad35)") (class "Default")
      (node (ref "J1") (pin "35") (pinfunction "MS_35") (pintype "passive"))
    )
    (net (code "118") (name "unconnected-(U1A-EXTRES-Pad96)") (class "Default")
      (node (ref "U1") (pin "96") (pinfunction "EXTRES_96") (pintype "input"))
    )
    (net (code "119") (name "unconnected-(U1A-QO0-Pad49)") (class "Default")
      (node (ref "U1") (pin "49") (pinfunction "QO0_49") (pintype "output"))
    )
    (net (code "120") (name "unconnected-(U1A-QO1-Pad50)") (class "Default")
      (node (ref "U1") (pin "50") (pinfunction "QO1_50") (pintype "output"))
    )
    (net (code "121") (name "unconnected-(U1A-QO2-Pad51)") (class "Default")
      (node (ref "U1") (pin "51") (pinfunction "QO2_51") (pintype "output"))
    )
    (net (code "122") (name "unconnected-(U1A-QO3-Pad52)") (class "Default")
      (node (ref "U1") (pin "52") (pinfunction "QO3_52") (pintype "output"))
    )
    (net (code "123") (name "unconnected-(U1A-QO4-Pad53)") (class "Default")
      (node (ref "U1") (pin "53") (pinfunction "QO4_53") (pintype "output"))
    )
    (net (code "124") (name "unconnected-(U1A-QO5-Pad54)") (class "Default")
      (node (ref "U1") (pin "54") (pinfunction "QO5_54") (pintype "output"))
    )
    (net (code "125") (name "unconnected-(U1A-QO6-Pad55)") (class "Default")
      (node (ref "U1") (pin "55") (pinfunction "QO6_55") (pintype "output"))
    )
    (net (code "126") (name "unconnected-(U1A-QO7-Pad56)") (class "Default")
      (node (ref "U1") (pin "56") (pinfunction "QO7_56") (pintype "output"))
    )
    (net (code "127") (name "unconnected-(U1A-QO8-Pad59)") (class "Default")
      (node (ref "U1") (pin "59") (pinfunction "QO8_59") (pintype "output"))
    )
    (net (code "128") (name "unconnected-(U1A-QO9-Pad60)") (class "Default")
      (node (ref "U1") (pin "60") (pinfunction "QO9_60") (pintype "output"))
    )
    (net (code "129") (name "unconnected-(U1A-QO10-Pad61)") (class "Default")
      (node (ref "U1") (pin "61") (pinfunction "QO10_61") (pintype "output"))
    )
    (net (code "130") (name "unconnected-(U1A-QO11-Pad62)") (class "Default")
      (node (ref "U1") (pin "62") (pinfunction "QO11_62") (pintype "output"))
    )
    (net (code "131") (name "unconnected-(U1A-QO12-Pad63)") (class "Default")
      (node (ref "U1") (pin "63") (pinfunction "QO12_63") (pintype "output"))
    )
    (net (code "132") (name "unconnected-(U1A-QO13-Pad64)") (class "Default")
      (node (ref "U1") (pin "64") (pinfunction "QO13_64") (pintype "output"))
    )
    (net (code "133") (name "unconnected-(U1A-QO14-Pad65)") (class "Default")
      (node (ref "U1") (pin "65") (pinfunction "QO14_65") (pintype "output"))
    )
    (net (code "134") (name "unconnected-(U1A-QO15-Pad66)") (class "Default")
      (node (ref "U1") (pin "66") (pinfunction "QO15_66") (pintype "output"))
    )
    (net (code "135") (name "unconnected-(U1A-QO16-Pad69)") (class "Default")
      (node (ref "U1") (pin "69") (pinfunction "QO16_69") (pintype "output"))
    )
    (net (code "136") (name "unconnected-(U1A-QO17-Pad70)") (class "Default")
      (node (ref "U1") (pin "70") (pinfunction "QO17_70") (pintype "output"))
    )
    (net (code "137") (name "unconnected-(U1A-QO18-Pad71)") (class "Default")
      (node (ref "U1") (pin "71") (pinfunction "QO18_71") (pintype "output"))
    )
    (net (code "138") (name "unconnected-(U1A-QO19-Pad72)") (class "Default")
      (node (ref "U1") (pin "72") (pinfunction "QO19_72") (pintype "output"))
    )
    (net (code "139") (name "unconnected-(U1A-QO20-Pad73)") (class "Default")
      (node (ref "U1") (pin "73") (pinfunction "QO20_73") (pintype "output"))
    )
    (net (code "140") (name "unconnected-(U1A-QO21-Pad74)") (class "Default")
      (node (ref "U1") (pin "74") (pinfunction "QO21_74") (pintype "output"))
    )
    (net (code "141") (name "unconnected-(U1A-QO22-Pad75)") (class "Default")
      (node (ref "U1") (pin "75") (pinfunction "QO22_75") (pintype "output"))
    )
    (net (code "142") (name "unconnected-(U1A-QO23-Pad77)") (class "Default")
      (node (ref "U1") (pin "77") (pinfunction "QO23_77") (pintype "output"))
    )
    (net (code "143") (name "unconnected-(X1A-CEC-Pad13)") (class "Default")
      (node (ref "X1") (pin "13") (pinfunction "CEC_13") (pintype "bidirectional"))
    )
    (net (code "144") (name "unconnected-(X1A-UTILITY-Pad14)") (class "Default")
      (node (ref "X1") (pin "14") (pinfunction "UTILITY_14") (pintype "bidirectional"))
    )
    (net (code "145") (name "unconnected-(X2-PadID)") (class "Default")
      (node (ref "X2") (pin "ID") (pinfunction "ID_ID") (pintype "bidirectional"))
    )
  )
)
